# IR_V_1_0_GERBER.net
KiCad netlist of a schematic drawn in EAGLE
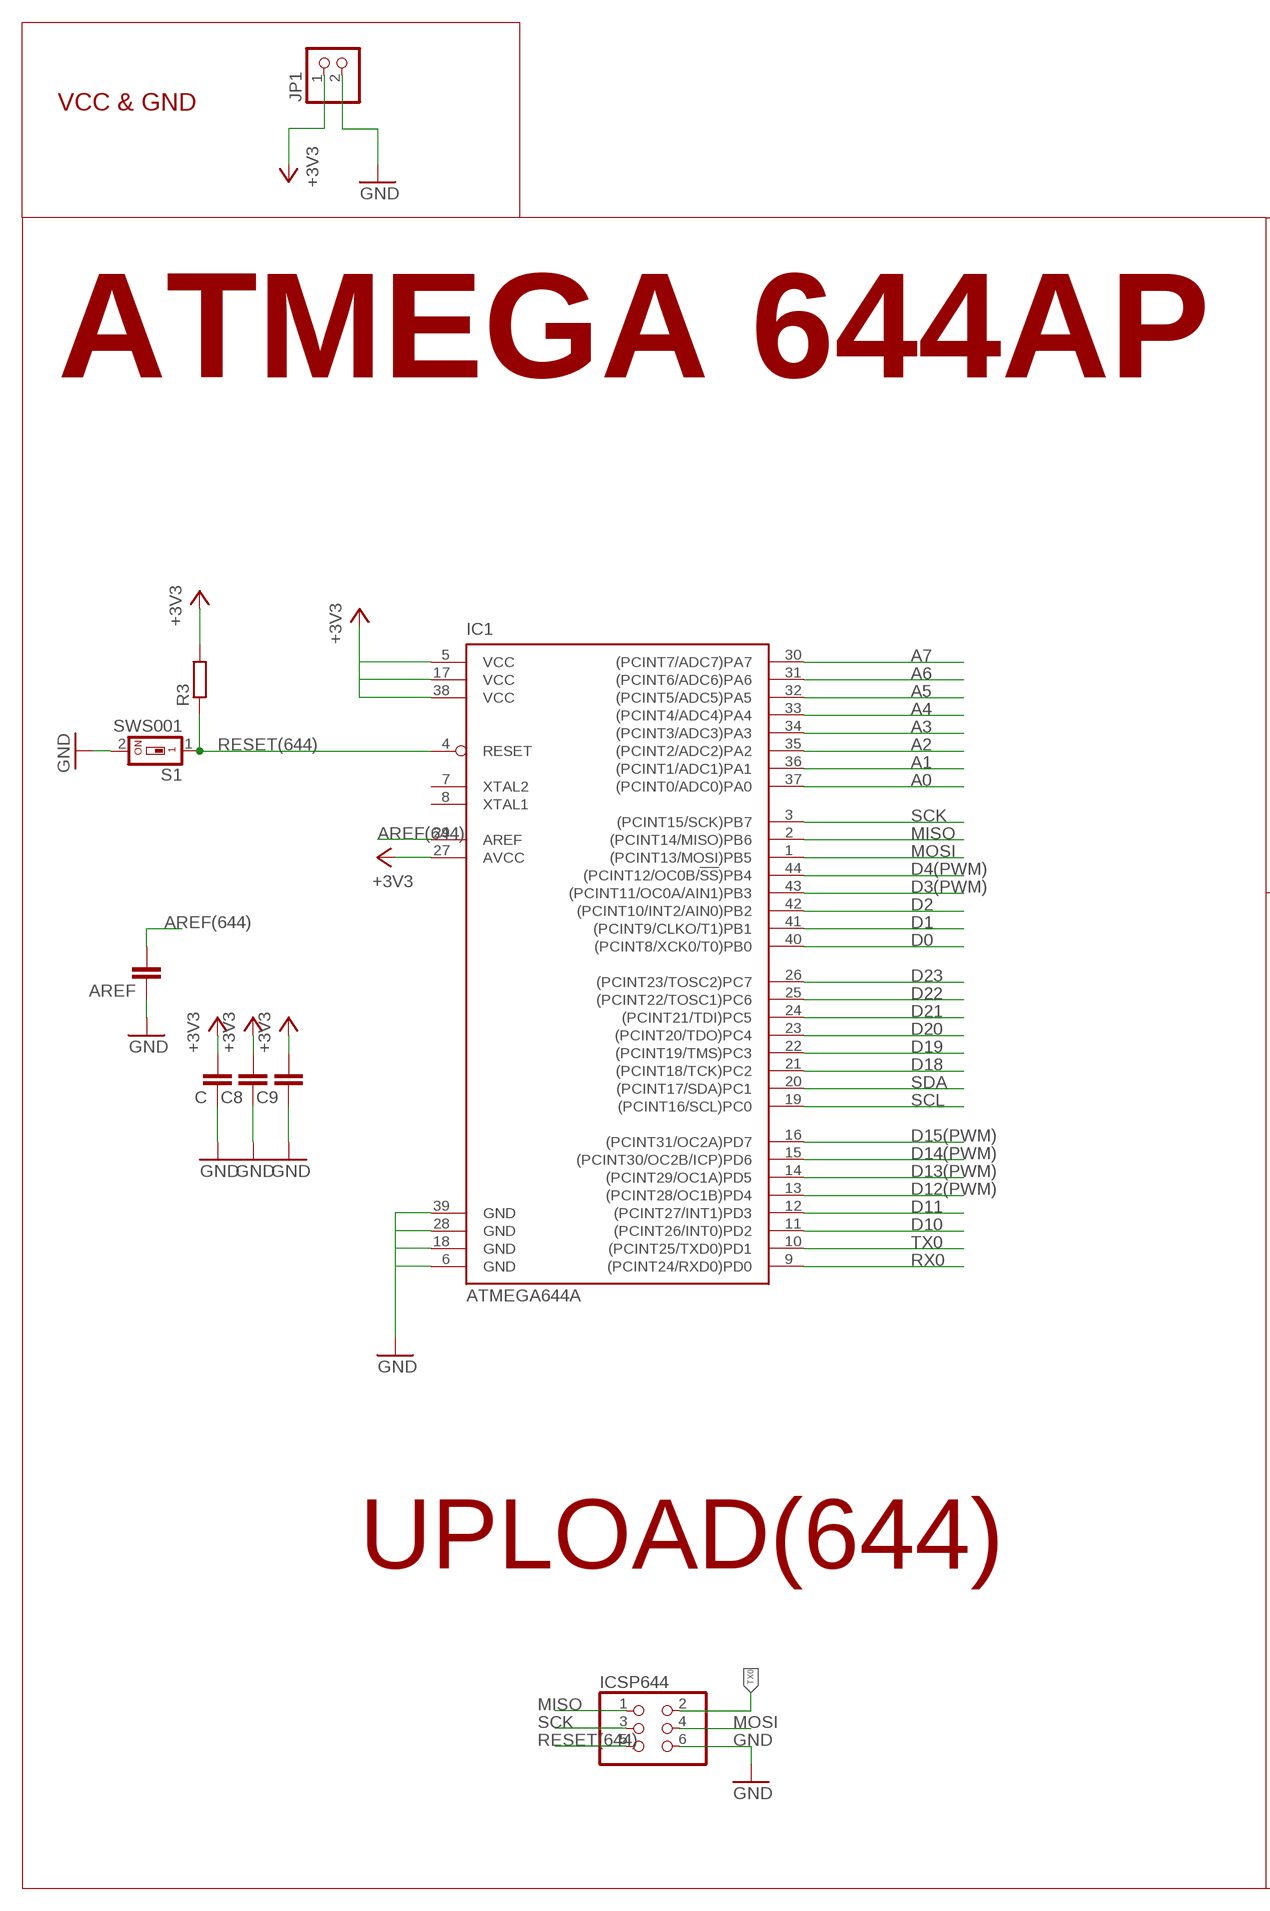
[diagram p0: schematic, sheet 1, part 1 of 2]
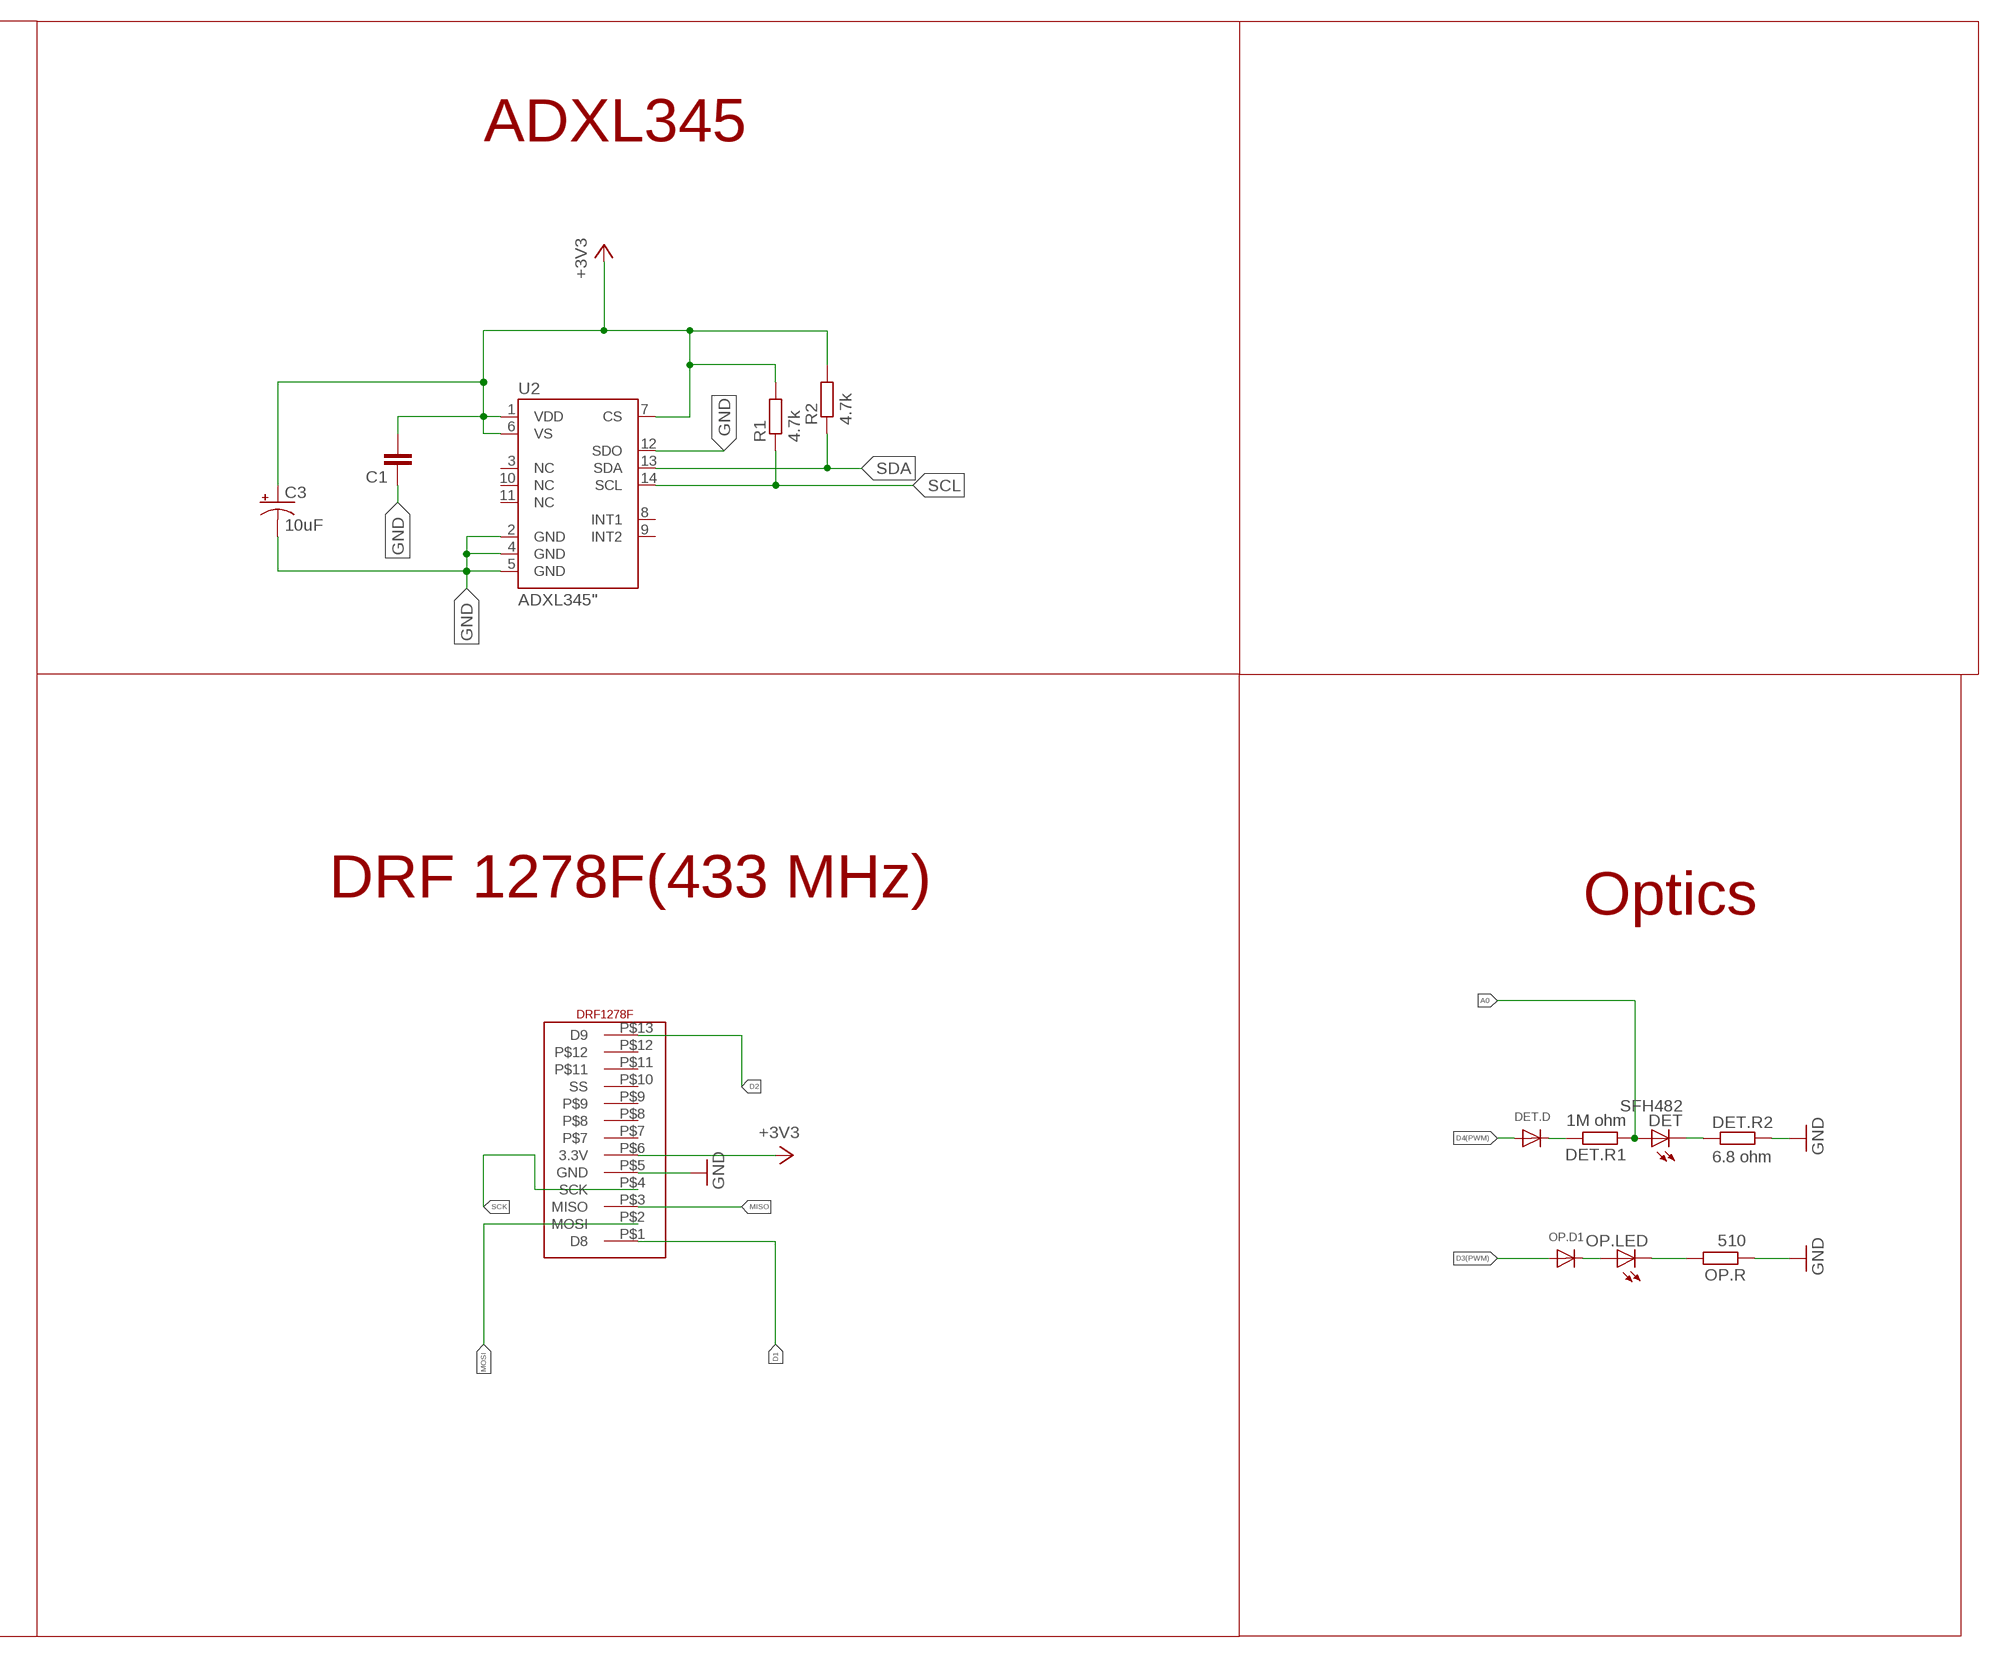
[diagram p1: schematic, sheet 1, part 2 of 2]

(export (version "E")
  (design (tool "Eeschema 10.0.6"))
  (components
    (comp (ref "AREF")
      (value "100nF")
      (footprint "eagle-import:C0805")
      (libsource (lib "eagle-import") (part "C-EUC0805"))
    )
    (comp (ref "C")
      (value "22 uF")
      (footprint "eagle-import:C0805")
      (libsource (lib "eagle-import") (part "C-EUC0805"))
    )
    (comp (ref "C1")
      (value "0.1uF")
      (footprint "eagle-import:C0805")
      (libsource (lib "eagle-import") (part "C-EUC0805"))
    )
    (comp (ref "C3")
      (value "10uF")
      (footprint "eagle-import:EIA3216")
      (libsource (lib "eagle-import") (part "CAP_POL1206"))
    )
    (comp (ref "C8")
      (value "100nF")
      (footprint "eagle-import:C0805")
      (libsource (lib "eagle-import") (part "C-EUC0805"))
    )
    (comp (ref "C9")
      (value "100nF")
      (footprint "eagle-import:C0805")
      (libsource (lib "eagle-import") (part "C-EUC0805"))
    )
    (comp (ref "DET")
      (value "SFH482")
      (footprint "eagle-import:SFH482")
      (libsource (lib "eagle-import") (part "SFH482"))
    )
    (comp (ref "DET.D")
      (value "DIODESOD-123")
      (footprint "eagle-import:SOD-123")
      (libsource (lib "eagle-import") (part "DIODESOD-123"))
    )
    (comp (ref "DET.R1")
      (value "1M ohm")
      (footprint "eagle-import:R0805")
      (libsource (lib "eagle-import") (part "R-EU_R0805"))
    )
    (comp (ref "DET.R2")
      (value "6.8 ohm")
      (footprint "eagle-import:R0805")
      (libsource (lib "eagle-import") (part "R-EU_R0805"))
    )
    (comp (ref "IC1")
      (value "ATMEGA644A")
      (footprint "eagle-import:TQFP44")
      (fields (field (name "MPN") "ATMEGA644PV-10AU"))
      (libsource (lib "eagle-import") (part "ATMEGA644A"))
    )
    (comp (ref "ICSP644")
      (value "PINHD-2X3")
      (footprint "eagle-import:2X03")
      (libsource (lib "eagle-import") (part "PINHD-2X3"))
    )
    (comp (ref "JP1")
      (value "PINHD-1X2")
      (footprint "eagle-import:1X02")
      (libsource (lib "eagle-import") (part "PINHD-1X2"))
    )
    (comp (ref "OP.D1")
      (value "DIODESOD-123")
      (footprint "eagle-import:SOD-123")
      (libsource (lib "eagle-import") (part "DIODESOD-123"))
    )
    (comp (ref "OP.LED")
      (value "LED3MM")
      (footprint "eagle-import:LED3MM")
      (libsource (lib "eagle-import") (part "LED3MM"))
    )
    (comp (ref "OP.R")
      (value "510")
      (footprint "eagle-import:R0805")
      (libsource (lib "eagle-import") (part "R-EU_R0805"))
    )
    (comp (ref "R1")
      (value "4.7k")
      (footprint "eagle-import:R0805")
      (libsource (lib "eagle-import") (part "R-EU_R0805"))
    )
    (comp (ref "R2")
      (value "4.7k")
      (footprint "eagle-import:R0805")
      (libsource (lib "eagle-import") (part "R-EU_R0805"))
    )
    (comp (ref "R3")
      (value "R-EU_R0805")
      (footprint "eagle-import:R0805")
      (libsource (lib "eagle-import") (part "R-EU_R0805"))
    )
    (comp (ref "S1")
      (value "SWS001")
      (footprint "eagle-import:SMS-001")
      (libsource (lib "eagle-import") (part "SWS001"))
    )
    (comp (ref "U$1")
      (value "DRF1278F")
      (footprint "eagle-import:DIP13")
      (libsource (lib "eagle-import") (part "DRF1278F"))
    )
    (comp (ref "U2")
      (value "ADXL345\"")
      (footprint "eagle-import:ADXL3451_1")
      (libsource (lib "eagle-import") (part "ADXL345{dblquote}"))
    )
  )
  (nets
    (net (code "1") (name "+3V3") (class "Default")
      (node (ref "C") (pin "2") (pinfunction "2_2") (pintype "passive"))
      (node (ref "C1") (pin "2") (pinfunction "2_2") (pintype "passive"))
      (node (ref "C3") (pin "A") (pinfunction "+_A") (pintype "passive"))
      (node (ref "C8") (pin "2") (pinfunction "2_2") (pintype "passive"))
      (node (ref "C9") (pin "2") (pinfunction "2_2") (pintype "passive"))
      (node (ref "IC1") (pin "17") (pinfunction "VCC_17") (pintype "power_in"))
      (node (ref "IC1") (pin "27") (pinfunction "AVCC_27") (pintype "power_in"))
      (node (ref "IC1") (pin "38") (pinfunction "VCC_38") (pintype "power_in"))
      (node (ref "IC1") (pin "5") (pinfunction "VCC_5") (pintype "power_in"))
      (node (ref "JP1") (pin "1") (pinfunction "1_1") (pintype "passive"))
      (node (ref "R1") (pin "2") (pinfunction "2_2") (pintype "passive"))
      (node (ref "R2") (pin "2") (pinfunction "2_2") (pintype "passive"))
      (node (ref "R3") (pin "2") (pinfunction "2_2") (pintype "passive"))
      (node (ref "U$1") (pin "P$6") (pinfunction "3.3V_P$6") (pintype "bidirectional"))
      (node (ref "U2") (pin "1") (pinfunction "VDD_1") (pintype "bidirectional"))
      (node (ref "U2") (pin "6") (pinfunction "VS_6") (pintype "bidirectional"))
      (node (ref "U2") (pin "7") (pinfunction "CS_7") (pintype "bidirectional"))
    )
    (net (code "2") (name "/A1") (class "Default")
      (node (ref "IC1") (pin "36") (pinfunction "(PCINT1/ADC1)PA1_36") (pintype "bidirectional"))
    )
    (net (code "3") (name "/A2") (class "Default")
      (node (ref "IC1") (pin "35") (pinfunction "(PCINT2/ADC2)PA2_35") (pintype "bidirectional"))
    )
    (net (code "4") (name "/A3") (class "Default")
      (node (ref "IC1") (pin "34") (pinfunction "(PCINT3/ADC3)PA3_34") (pintype "bidirectional"))
    )
    (net (code "5") (name "/A4") (class "Default")
      (node (ref "IC1") (pin "33") (pinfunction "(PCINT4/ADC4)PA4_33") (pintype "bidirectional"))
    )
    (net (code "6") (name "/A5") (class "Default")
      (node (ref "IC1") (pin "32") (pinfunction "(PCINT5/ADC5)PA5_32") (pintype "bidirectional"))
    )
    (net (code "7") (name "/A6") (class "Default")
      (node (ref "IC1") (pin "31") (pinfunction "(PCINT6/ADC6)PA6_31") (pintype "bidirectional"))
    )
    (net (code "8") (name "/A7") (class "Default")
      (node (ref "IC1") (pin "30") (pinfunction "(PCINT7/ADC7)PA7_30") (pintype "bidirectional"))
    )
    (net (code "9") (name "/AREF(644)") (class "Default")
      (node (ref "AREF") (pin "2") (pinfunction "2_2") (pintype "passive"))
      (node (ref "IC1") (pin "29") (pinfunction "AREF_29") (pintype "passive"))
    )
    (net (code "10") (name "/D0") (class "Default")
      (node (ref "IC1") (pin "40") (pinfunction "(PCINT8/XCK0/T0)PB0_40") (pintype "bidirectional"))
    )
    (net (code "11") (name "/D10") (class "Default")
      (node (ref "IC1") (pin "11") (pinfunction "(PCINT26/INT0)PD2_11") (pintype "bidirectional"))
    )
    (net (code "12") (name "/D11") (class "Default")
      (node (ref "IC1") (pin "12") (pinfunction "(PCINT27/INT1)PD3_12") (pintype "bidirectional"))
    )
    (net (code "13") (name "/D12(PWM)") (class "Default")
      (node (ref "IC1") (pin "13") (pinfunction "(PCINT28/OC1B)PD4_13") (pintype "bidirectional"))
    )
    (net (code "14") (name "/D13(PWM)") (class "Default")
      (node (ref "IC1") (pin "14") (pinfunction "(PCINT29/OC1A)PD5_14") (pintype "bidirectional"))
    )
    (net (code "15") (name "/D14(PWM)") (class "Default")
      (node (ref "IC1") (pin "15") (pinfunction "(PCINT30/OC2B/ICP)PD6_15") (pintype "bidirectional"))
    )
    (net (code "16") (name "/D15(PWM)") (class "Default")
      (node (ref "IC1") (pin "16") (pinfunction "(PCINT31/OC2A)PD7_16") (pintype "bidirectional"))
    )
    (net (code "17") (name "/D18") (class "Default")
      (node (ref "IC1") (pin "21") (pinfunction "(PCINT18/TCK)PC2_21") (pintype "output"))
    )
    (net (code "18") (name "/D19") (class "Default")
      (node (ref "IC1") (pin "22") (pinfunction "(PCINT19/TMS)PC3_22") (pintype "output"))
    )
    (net (code "19") (name "/D20") (class "Default")
      (node (ref "IC1") (pin "23") (pinfunction "(PCINT20/TDO)PC4_23") (pintype "output"))
    )
    (net (code "20") (name "/D21") (class "Default")
      (node (ref "IC1") (pin "24") (pinfunction "(PCINT21/TDI)PC5_24") (pintype "output"))
    )
    (net (code "21") (name "/D22") (class "Default")
      (node (ref "IC1") (pin "25") (pinfunction "(PCINT22/TOSC1)PC6_25") (pintype "output"))
    )
    (net (code "22") (name "/D23") (class "Default")
      (node (ref "IC1") (pin "26") (pinfunction "(PCINT23/TOSC2)PC7_26") (pintype "output"))
    )
    (net (code "23") (name "/RESET(644)") (class "Default")
      (node (ref "IC1") (pin "4") (pinfunction "RESET_4") (pintype "input"))
      (node (ref "ICSP644") (pin "5") (pinfunction "5_5") (pintype "passive"))
      (node (ref "R3") (pin "1") (pinfunction "1_1") (pintype "passive"))
      (node (ref "S1") (pin "1") (pinfunction "1_1") (pintype "passive"))
    )
    (net (code "24") (name "/RX0") (class "Default")
      (node (ref "IC1") (pin "9") (pinfunction "(PCINT24/RXD0)PD0_9") (pintype "bidirectional"))
    )
    (net (code "25") (name "A0") (class "Default")
      (node (ref "DET") (pin "A") (pinfunction "A_A") (pintype "passive"))
      (node (ref "DET.R1") (pin "1") (pinfunction "1_1") (pintype "passive"))
      (node (ref "IC1") (pin "37") (pinfunction "(PCINT0/ADC0)PA0_37") (pintype "bidirectional"))
    )
    (net (code "26") (name "D1") (class "Default")
      (node (ref "IC1") (pin "41") (pinfunction "(PCINT9/CLKO/T1)PB1_41") (pintype "bidirectional"))
      (node (ref "U$1") (pin "P$1") (pinfunction "D8_P$1") (pintype "bidirectional"))
    )
    (net (code "27") (name "D2") (class "Default")
      (node (ref "IC1") (pin "42") (pinfunction "(PCINT10/INT2/AIN0)PB2_42") (pintype "bidirectional"))
      (node (ref "U$1") (pin "P$13") (pinfunction "D9_P$13") (pintype "bidirectional"))
    )
    (net (code "28") (name "D3(PWM)") (class "Default")
      (node (ref "IC1") (pin "43") (pinfunction "(PCINT11/OC0A/AIN1)PB3_43") (pintype "bidirectional"))
      (node (ref "OP.D1") (pin "A") (pinfunction "A_A") (pintype "passive"))
    )
    (net (code "29") (name "D4(PWM)") (class "Default")
      (node (ref "DET.D") (pin "A") (pinfunction "A_A") (pintype "passive"))
      (node (ref "IC1") (pin "44") (pinfunction "(PCINT12/OC0B/~{SS})PB4_44") (pintype "bidirectional"))
    )
    (net (code "30") (name "GND") (class "Default")
      (node (ref "AREF") (pin "1") (pinfunction "1_1") (pintype "passive"))
      (node (ref "C") (pin "1") (pinfunction "1_1") (pintype "passive"))
      (node (ref "C1") (pin "1") (pinfunction "1_1") (pintype "passive"))
      (node (ref "C3") (pin "C") (pinfunction "-_C") (pintype "passive"))
      (node (ref "C8") (pin "1") (pinfunction "1_1") (pintype "passive"))
      (node (ref "C9") (pin "1") (pinfunction "1_1") (pintype "passive"))
      (node (ref "DET.R2") (pin "2") (pinfunction "2_2") (pintype "passive"))
      (node (ref "IC1") (pin "18") (pinfunction "GND_18") (pintype "power_in"))
      (node (ref "IC1") (pin "28") (pinfunction "GND_28") (pintype "power_in"))
      (node (ref "IC1") (pin "39") (pinfunction "GND_39") (pintype "power_in"))
      (node (ref "IC1") (pin "6") (pinfunction "GND_6") (pintype "power_in"))
      (node (ref "ICSP644") (pin "6") (pinfunction "6_6") (pintype "passive"))
      (node (ref "JP1") (pin "2") (pinfunction "2_2") (pintype "passive"))
      (node (ref "OP.R") (pin "1") (pinfunction "1_1") (pintype "passive"))
      (node (ref "S1") (pin "2") (pinfunction "2_2") (pintype "passive"))
      (node (ref "U$1") (pin "P$5") (pinfunction "GND_P$5") (pintype "bidirectional"))
      (node (ref "U2") (pin "12") (pinfunction "SDO_12") (pintype "bidirectional"))
      (node (ref "U2") (pin "2") (pinfunction "GND_2") (pintype "bidirectional"))
      (node (ref "U2") (pin "4") (pinfunction "GND_4") (pintype "bidirectional"))
      (node (ref "U2") (pin "5") (pinfunction "GND_5") (pintype "bidirectional"))
    )
    (net (code "31") (name "MISO") (class "Default")
      (node (ref "IC1") (pin "2") (pinfunction "(PCINT14/MISO)PB6_2") (pintype "bidirectional"))
      (node (ref "ICSP644") (pin "1") (pinfunction "1_1") (pintype "passive"))
      (node (ref "U$1") (pin "P$3") (pinfunction "MISO_P$3") (pintype "bidirectional"))
    )
    (net (code "32") (name "MOSI") (class "Default")
      (node (ref "IC1") (pin "1") (pinfunction "(PCINT13/MOSI)PB5_1") (pintype "bidirectional"))
      (node (ref "ICSP644") (pin "4") (pinfunction "4_4") (pintype "passive"))
      (node (ref "U$1") (pin "P$2") (pinfunction "MOSI_P$2") (pintype "bidirectional"))
    )
    (net (code "33") (name "Net-(DET-C)") (class "Default")
      (node (ref "DET") (pin "K") (pinfunction "C_K") (pintype "passive"))
      (node (ref "DET.R2") (pin "1") (pinfunction "1_1") (pintype "passive"))
    )
    (net (code "34") (name "Net-(DET.D-PadC)") (class "Default")
      (node (ref "DET.D") (pin "C") (pinfunction "C_C") (pintype "passive"))
      (node (ref "DET.R1") (pin "2") (pinfunction "2_2") (pintype "passive"))
    )
    (net (code "35") (name "Net-(OP.D1-PadC)") (class "Default")
      (node (ref "OP.D1") (pin "C") (pinfunction "C_C") (pintype "passive"))
      (node (ref "OP.LED") (pin "A") (pinfunction "A_A") (pintype "passive"))
    )
    (net (code "36") (name "Net-(OP.LED-C)") (class "Default")
      (node (ref "OP.LED") (pin "K") (pinfunction "C_K") (pintype "passive"))
      (node (ref "OP.R") (pin "2") (pinfunction "2_2") (pintype "passive"))
    )
    (net (code "37") (name "SCK") (class "Default")
      (node (ref "IC1") (pin "3") (pinfunction "(PCINT15/SCK)PB7_3") (pintype "bidirectional"))
      (node (ref "ICSP644") (pin "3") (pinfunction "3_3") (pintype "passive"))
      (node (ref "U$1") (pin "P$4") (pinfunction "SCK_P$4") (pintype "bidirectional"))
    )
    (net (code "38") (name "SCL") (class "Default")
      (node (ref "IC1") (pin "19") (pinfunction "(PCINT16/SCL)PC0_19") (pintype "output"))
      (node (ref "R1") (pin "1") (pinfunction "1_1") (pintype "passive"))
      (node (ref "U2") (pin "14") (pinfunction "SCL_14") (pintype "bidirectional"))
    )
    (net (code "39") (name "SDA") (class "Default")
      (node (ref "IC1") (pin "20") (pinfunction "(PCINT17/SDA)PC1_20") (pintype "output"))
      (node (ref "R2") (pin "1") (pinfunction "1_1") (pintype "passive"))
      (node (ref "U2") (pin "13") (pinfunction "SDA_13") (pintype "bidirectional"))
    )
    (net (code "40") (name "TX0") (class "Default")
      (node (ref "IC1") (pin "10") (pinfunction "(PCINT25/TXD0)PD1_10") (pintype "bidirectional"))
      (node (ref "ICSP644") (pin "2") (pinfunction "2_2") (pintype "passive"))
    )
    (net (code "41") (name "unconnected-(IC1-XTAL1-Pad8)") (class "Default")
      (node (ref "IC1") (pin "8") (pinfunction "XTAL1_8") (pintype "bidirectional"))
    )
    (net (code "42") (name "unconnected-(IC1-XTAL2-Pad7)") (class "Default")
      (node (ref "IC1") (pin "7") (pinfunction "XTAL2_7") (pintype "bidirectional"))
    )
    (net (code "43") (name "unconnected-(U$1-PadP$7)") (class "Default")
      (node (ref "U$1") (pin "P$7") (pinfunction "P$7_P$7") (pintype "bidirectional"))
    )
    (net (code "44") (name "unconnected-(U$1-PadP$8)") (class "Default")
      (node (ref "U$1") (pin "P$8") (pinfunction "P$8_P$8") (pintype "bidirectional"))
    )
    (net (code "45") (name "unconnected-(U$1-PadP$9)") (class "Default")
      (node (ref "U$1") (pin "P$9") (pinfunction "P$9_P$9") (pintype "bidirectional"))
    )
    (net (code "46") (name "unconnected-(U$1-PadP$11)") (class "Default")
      (node (ref "U$1") (pin "P$11") (pinfunction "P$11_P$11") (pintype "bidirectional"))
    )
    (net (code "47") (name "unconnected-(U$1-PadP$12)") (class "Default")
      (node (ref "U$1") (pin "P$12") (pinfunction "P$12_P$12") (pintype "bidirectional"))
    )
    (net (code "48") (name "unconnected-(U$1-SS-PadP$10)") (class "Default")
      (node (ref "U$1") (pin "P$10") (pinfunction "SS_P$10") (pintype "bidirectional"))
    )
    (net (code "49") (name "unconnected-(U2-INT1-Pad8)") (class "Default")
      (node (ref "U2") (pin "8") (pinfunction "INT1_8") (pintype "bidirectional"))
    )
    (net (code "50") (name "unconnected-(U2-INT2-Pad9)") (class "Default")
      (node (ref "U2") (pin "9") (pinfunction "INT2_9") (pintype "bidirectional"))
    )
    (net (code "51") (name "unconnected-(U2-NC-Pad3)") (class "Default")
      (node (ref "U2") (pin "3") (pinfunction "NC_3") (pintype "bidirectional"))
    )
    (net (code "52") (name "unconnected-(U2-NC-Pad10)") (class "Default")
      (node (ref "U2") (pin "10") (pinfunction "NC_10") (pintype "bidirectional"))
    )
    (net (code "53") (name "unconnected-(U2-NC-Pad11)") (class "Default")
      (node (ref "U2") (pin "11") (pinfunction "NC_11") (pintype "bidirectional"))
    )
  )
)
